# iot_macuman_board.net
KiCad netlist of a schematic drawn in Altium Designer
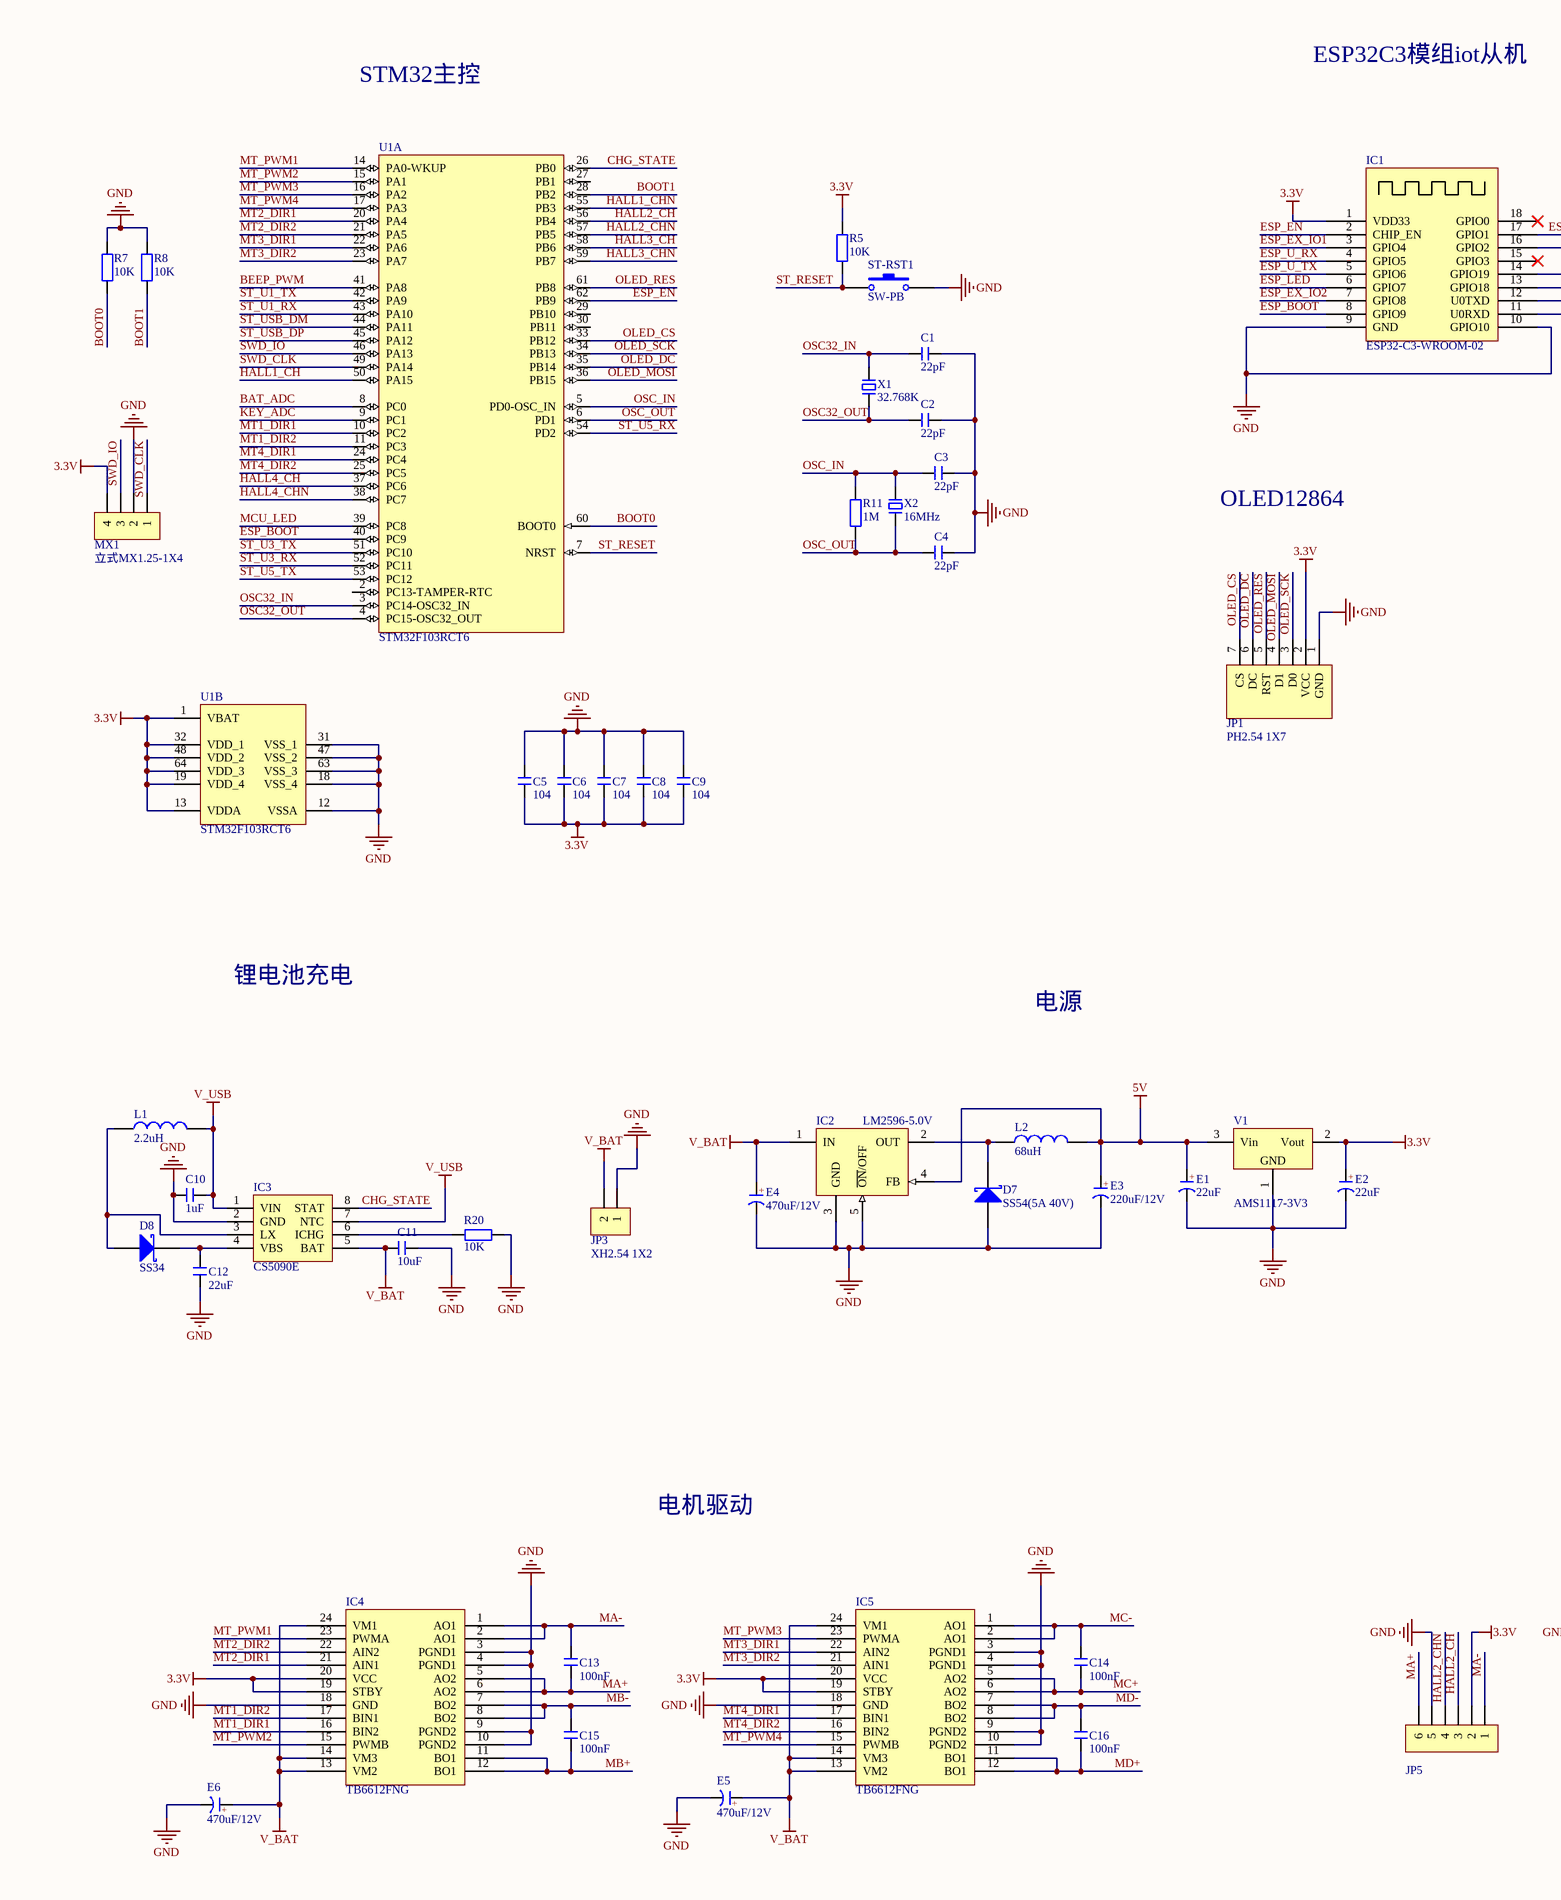
[diagram p0: iot_macuman_board.SchDoc, left]
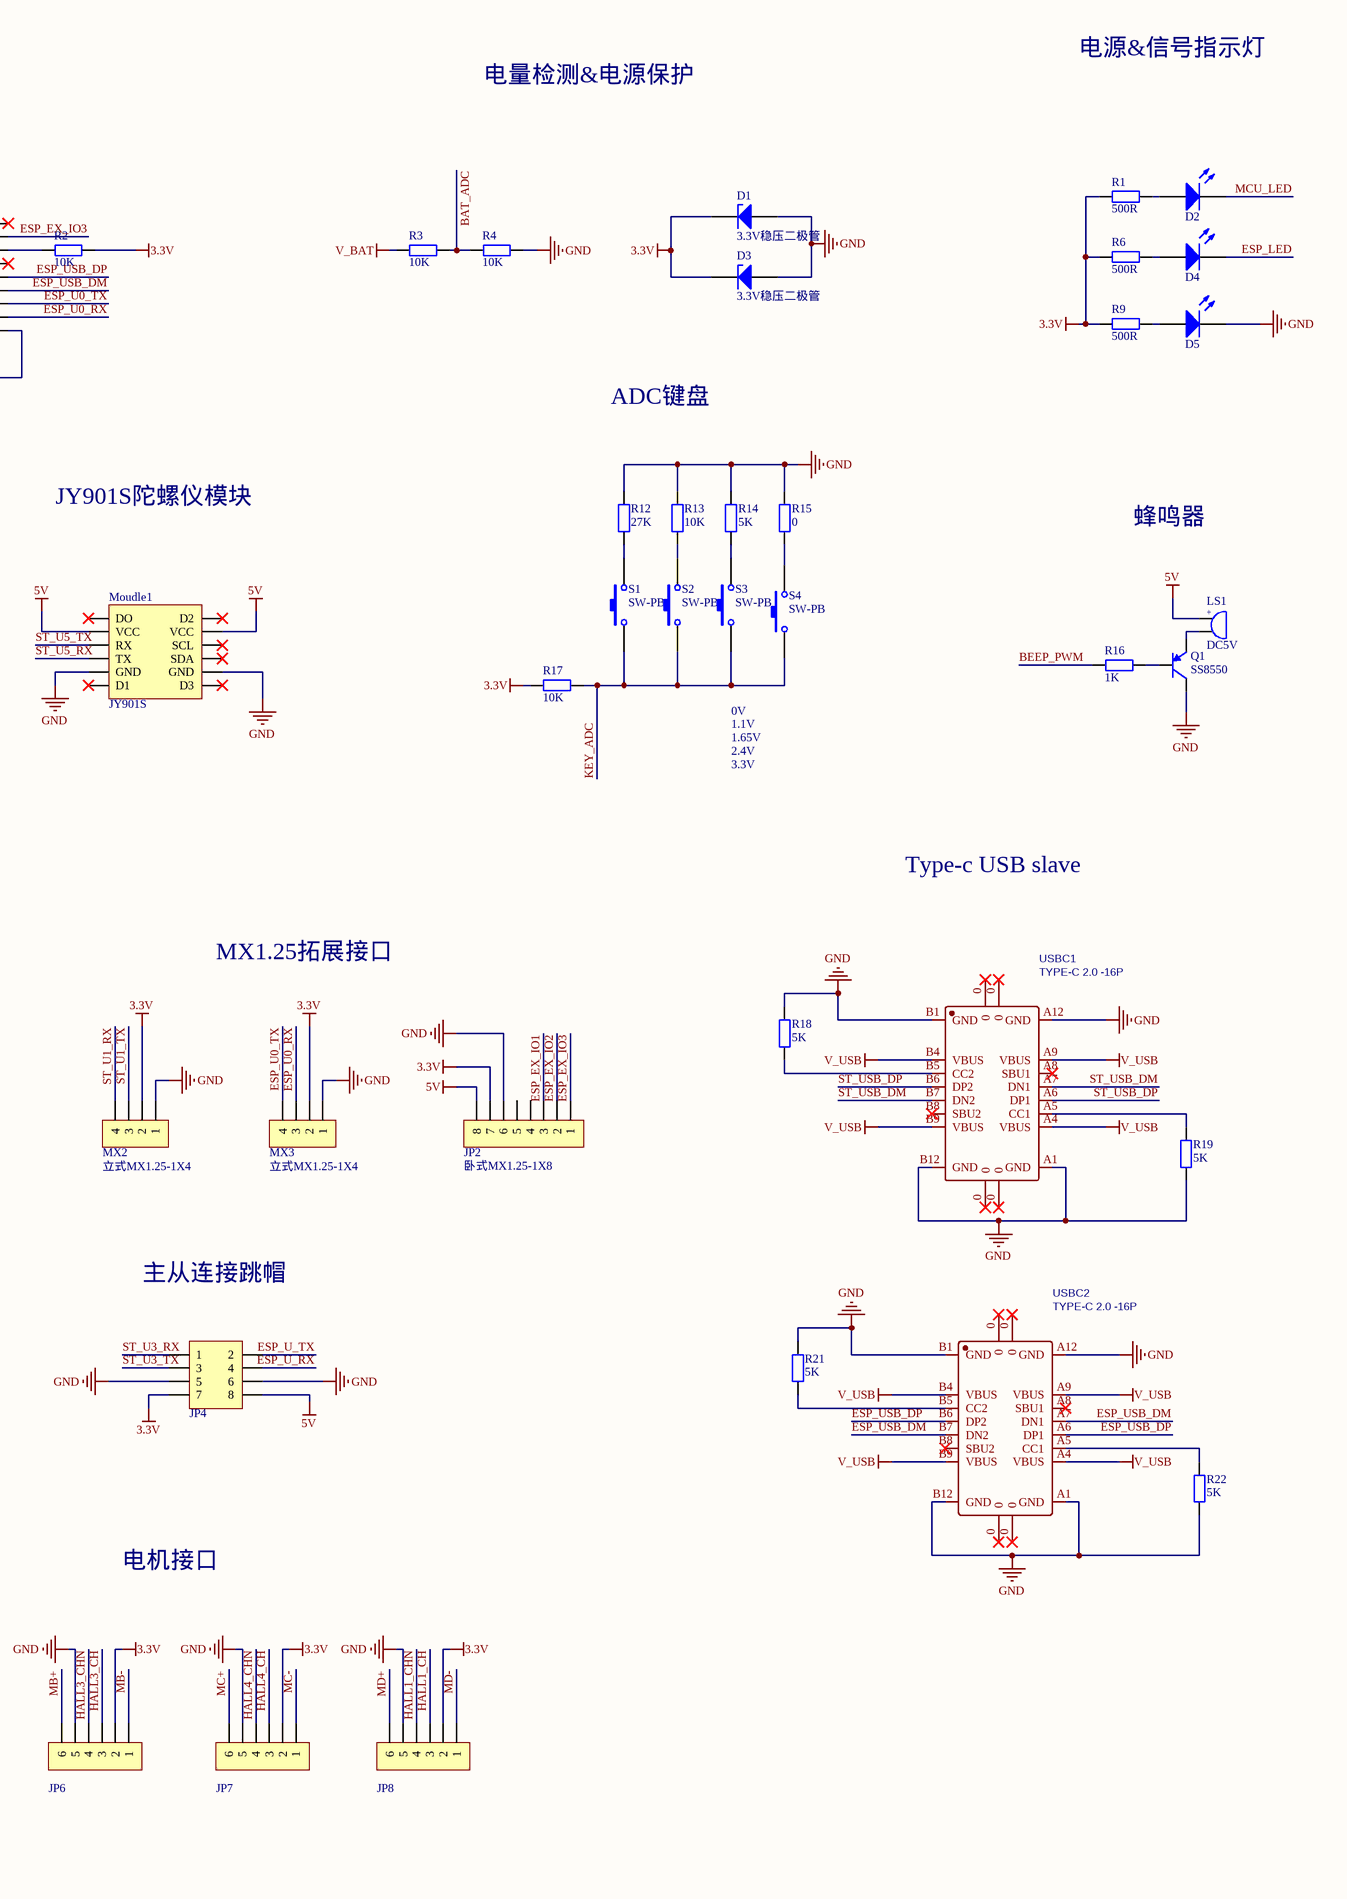
[diagram p1: iot_macuman_board.SchDoc, right]

(export (version "E")
  (design (tool "Eeschema 10.0.6"))
  (components
    (comp (ref "C1")
      (value "22pF")
      (footprint "C 0402")
      (description "贴片电容")
      (libsource (lib "核心板1") (part "C"))
    )
    (comp (ref "C2")
      (value "22pF")
      (footprint "C 0402")
      (description "贴片电容")
      (libsource (lib "核心板1") (part "C"))
    )
    (comp (ref "C3")
      (value "22pF")
      (footprint "C 0402")
      (description "贴片电容")
      (libsource (lib "核心板1") (part "C"))
    )
    (comp (ref "C4")
      (value "22pF")
      (footprint "C 0402")
      (description "贴片电容")
      (libsource (lib "核心板1") (part "C"))
    )
    (comp (ref "C5")
      (value "104")
      (footprint "C 0402")
      (description "贴片电容")
      (libsource (lib "核心板1") (part "C"))
    )
    (comp (ref "C6")
      (value "104")
      (footprint "C 0402")
      (description "贴片电容")
      (libsource (lib "核心板1") (part "C"))
    )
    (comp (ref "C7")
      (value "104")
      (footprint "C 0402")
      (description "贴片电容")
      (libsource (lib "核心板1") (part "C"))
    )
    (comp (ref "C8")
      (value "104")
      (footprint "C 0402")
      (description "贴片电容")
      (libsource (lib "核心板1") (part "C"))
    )
    (comp (ref "C9")
      (value "104")
      (footprint "C 0402")
      (description "贴片电容")
      (libsource (lib "核心板1") (part "C"))
    )
    (comp (ref "C10")
      (value "1uF")
      (footprint "C 0402")
      (description "贴片电容")
      (libsource (lib "核心板1") (part "C"))
    )
    (comp (ref "C11")
      (value "10uF")
      (footprint "C 0402")
      (description "贴片电容")
      (libsource (lib "核心板1") (part "C"))
    )
    (comp (ref "C12")
      (value "22uF")
      (footprint "C 0603_M")
      (description "贴片电容")
      (libsource (lib "核心板1") (part "C"))
    )
    (comp (ref "C13")
      (value "100nF")
      (footprint "C 0402")
      (description "贴片电容")
      (libsource (lib "核心板1") (part "C"))
    )
    (comp (ref "C14")
      (value "100nF")
      (footprint "C 0402")
      (description "贴片电容")
      (libsource (lib "核心板1") (part "C"))
    )
    (comp (ref "C15")
      (value "100nF")
      (footprint "C 0402")
      (description "贴片电容")
      (libsource (lib "核心板1") (part "C"))
    )
    (comp (ref "C16")
      (value "100nF")
      (footprint "C 0402")
      (description "贴片电容")
      (libsource (lib "核心板1") (part "C"))
    )
    (comp (ref "D1")
      (value "3.3V稳压二极管")
      (footprint "LL34")
      (description "Zener Diode")
      (libsource (lib "核心板1") (part "稳压二极管"))
    )
    (comp (ref "D2")
      (value "LED")
      (footprint "LED 0805G")
      (description "发光二极管")
      (libsource (lib "核心板1") (part "LED"))
    )
    (comp (ref "D3")
      (value "3.3V稳压二极管")
      (footprint "LL34")
      (description "Zener Diode")
      (libsource (lib "核心板1") (part "稳压二极管"))
    )
    (comp (ref "D4")
      (value "LED")
      (footprint "LED 0805G")
      (description "发光二极管")
      (libsource (lib "核心板1") (part "LED"))
    )
    (comp (ref "D5")
      (value "LED")
      (footprint "LED 0805G")
      (description "发光二极管")
      (libsource (lib "核心板1") (part "LED"))
    )
    (comp (ref "D7")
      (value "SS54(5A 40V)")
      (footprint "SMB")
      (description "肖特基二极管")
      (libsource (lib "核心板1") (part "1N5819"))
    )
    (comp (ref "D8")
      (value "SS34")
      (footprint "SMA")
      (description "肖特基二极管")
      (libsource (lib "核心板1") (part "SS34"))
    )
    (comp (ref "E1")
      (value "22uF")
      (footprint "CM C(5*5.4)")
      (description "贴片固态电容")
      (libsource (lib "0.1 - 电阻-电容-电感") (part "CS_SMD"))
    )
    (comp (ref "E2")
      (value "22uF")
      (footprint "CM C(5*5.4)")
      (description "贴片固态电容")
      (libsource (lib "0.1 - 电阻-电容-电感") (part "CS_SMD"))
    )
    (comp (ref "E3")
      (value "220uF/12V")
      (footprint "CM C(5*5.4)")
      (description "贴片固态电容")
      (libsource (lib "0.1 - 电阻-电容-电感") (part "CS_SMD"))
    )
    (comp (ref "E4")
      (value "470uF/12V")
      (footprint "CM E(8*10.2)")
      (description "贴片电解电容")
      (libsource (lib "*") (part "CE_SMD"))
    )
    (comp (ref "E5")
      (value "470uF/12V")
      (footprint "CM E(8*10.2)")
      (description "贴片电解电容")
      (libsource (lib "") (part "CE_SMD_1"))
    )
    (comp (ref "E6")
      (value "470uF/12V")
      (footprint "CM E(8*10.2)")
      (description "贴片电解电容")
      (libsource (lib "") (part "CE_SMD_1"))
    )
    (comp (ref "IC1")
      (value "ESP32-C3-WROOM-02")
      (footprint "ESP32-C3-WROOM-02")
      (description "ESP32C3模组")
      (libsource (lib "核心板1") (part "ESP32-C3-WROOM-02"))
    )
    (comp (ref "IC2")
      (value "LM2596-5.0V")
      (footprint "TO263-5A")
      (description "DC降压芯片")
      (libsource (lib "核心板1") (part "LM2596-5.0"))
    )
    (comp (ref "IC3")
      (value "CS5090E")
      (footprint "SOP8_M")
      (description "8.4V锂电池充电芯片")
      (libsource (lib "核心板1") (part "CS5090E"))
    )
    (comp (ref "IC4")
      (value "TB6612FNG")
      (footprint "SSOP24")
      (description "电机驱动IC")
      (libsource (lib "核心板1") (part "TB6612FNG"))
    )
    (comp (ref "IC5")
      (value "TB6612FNG")
      (footprint "SSOP24")
      (description "电机驱动IC")
      (libsource (lib "核心板1") (part "TB6612FNG"))
    )
    (comp (ref "JP1")
      (value "PH2.54 1X7")
      (footprint "HDR2.54-LI-7P")
      (description "12864 点阵屏")
      (libsource (lib "核心板1") (part "OLED 1.3-12864_7pin"))
    )
    (comp (ref "JP2")
      (value "卧式MX1.25-1X8")
      (footprint "MX 1.25-WS-8P")
      (description "8P接插件")
      (libsource (lib "iot_macuman_board") (part "Header 8"))
    )
    (comp (ref "JP3")
      (value "XH2.54 1X2")
      (footprint "XH2.54-LI-2P")
      (libsource (lib "核心板1") (part "Header 2"))
    )
    (comp (ref "JP4")
      (value "PH2.54 4X2")
      (footprint "HDR2.54-LI-2X4P")
      (description "4*2P接插件")
      (libsource (lib "核心板1") (part "Header 4X2"))
    )
    (comp (ref "JP5")
      (value "电机接口")
      (footprint "XH2.54-WI-6P")
      (description "6P接插件")
      (libsource (lib "核心板1") (part "Header 6"))
    )
    (comp (ref "JP6")
      (value "电机接口")
      (footprint "XH2.54-WI-6P")
      (description "6P接插件")
      (libsource (lib "核心板1") (part "Header 6"))
    )
    (comp (ref "JP7")
      (value "电机接口")
      (footprint "XH2.54-WI-6P")
      (description "6P接插件")
      (libsource (lib "核心板1") (part "Header 6"))
    )
    (comp (ref "JP8")
      (value "电机接口")
      (footprint "XH2.54-WI-6P")
      (description "6P接插件")
      (libsource (lib "核心板1") (part "Header 6"))
    )
    (comp (ref "L1")
      (value "2.2uH")
      (footprint "CD32")
      (description "小功率贴片电感")
      (libsource (lib "核心板1") (part "L"))
    )
    (comp (ref "L2")
      (value "68uH")
      (footprint "CD32")
      (description "小功率贴片电感")
      (libsource (lib "核心板1") (part "L"))
    )
    (comp (ref "LS1")
      (value "DC5V")
      (footprint "蜂鸣器(脚距6.5)")
      (description "蜂鸣器")
      (libsource (lib "核心板1") (part "BEEP"))
    )
    (comp (ref "Moudle1")
      (value "JY901S")
      (footprint "JY901S")
      (libsource (lib "iot_macuman_board") (part "JY901S"))
    )
    (comp (ref "MX1")
      (value "立式MX1.25-1X4")
      (footprint "MX 1.25-LS-4P")
      (description "4P接插件")
      (libsource (lib "核心板1") (part "Header 4"))
    )
    (comp (ref "MX2")
      (value "立式MX1.25-1X4")
      (footprint "MX 1.25-LS-4P")
      (description "4P接插件")
      (libsource (lib "核心板1") (part "Header 4"))
    )
    (comp (ref "MX3")
      (value "立式MX1.25-1X4")
      (footprint "MX 1.25-LS-4P")
      (description "4P接插件")
      (libsource (lib "核心板1") (part "Header 4"))
    )
    (comp (ref "Q1")
      (value "SS8550")
      (footprint "sot-23")
      (description "高频放大-PNP型")
      (libsource (lib "*") (part "8550-SMD"))
    )
    (comp (ref "R1")
      (value "500R")
      (footprint "R 0402")
      (description "贴片电阻")
      (libsource (lib "核心板1") (part "R"))
    )
    (comp (ref "R2")
      (value "10K")
      (footprint "R 0402")
      (description "贴片电阻")
      (libsource (lib "核心板1") (part "R"))
    )
    (comp (ref "R3")
      (value "10K")
      (footprint "R 0402")
      (description "贴片电阻")
      (libsource (lib "核心板1") (part "R"))
    )
    (comp (ref "R4")
      (value "10K")
      (footprint "R 0402")
      (description "贴片电阻")
      (libsource (lib "核心板1") (part "R"))
    )
    (comp (ref "R5")
      (value "10K")
      (footprint "R 0402")
      (description "贴片电阻")
      (libsource (lib "核心板1") (part "R"))
    )
    (comp (ref "R6")
      (value "500R")
      (footprint "R 0402")
      (description "贴片电阻")
      (libsource (lib "核心板1") (part "R"))
    )
    (comp (ref "R7")
      (value "10K")
      (footprint "R 0402")
      (description "贴片电阻")
      (libsource (lib "核心板1") (part "R"))
    )
    (comp (ref "R8")
      (value "10K")
      (footprint "R 0402")
      (description "贴片电阻")
      (libsource (lib "核心板1") (part "R"))
    )
    (comp (ref "R9")
      (value "500R")
      (footprint "R 0402")
      (description "贴片电阻")
      (libsource (lib "核心板1") (part "R"))
    )
    (comp (ref "R11")
      (value "1M")
      (footprint "R 0402")
      (description "贴片电阻")
      (libsource (lib "核心板1") (part "R"))
    )
    (comp (ref "R12")
      (value "27K")
      (footprint "R 0402")
      (description "贴片电阻")
      (libsource (lib "核心板1") (part "R"))
    )
    (comp (ref "R13")
      (value "10K")
      (footprint "R 0402")
      (description "贴片电阻")
      (libsource (lib "核心板1") (part "R"))
    )
    (comp (ref "R14")
      (value "5K")
      (footprint "R 0402")
      (description "贴片电阻")
      (libsource (lib "核心板1") (part "R"))
    )
    (comp (ref "R15")
      (value "0")
      (footprint "R 0402")
      (description "贴片电阻")
      (libsource (lib "核心板1") (part "R"))
    )
    (comp (ref "R16")
      (value "1K")
      (footprint "R 0402")
      (description "贴片电阻")
      (libsource (lib "核心板1") (part "R"))
    )
    (comp (ref "R17")
      (value "10K")
      (footprint "R 0402")
      (description "贴片电阻")
      (libsource (lib "核心板1") (part "R"))
    )
    (comp (ref "R18")
      (value "5K")
      (footprint "R 0402")
      (description "贴片电阻")
      (libsource (lib "核心板1") (part "R"))
    )
    (comp (ref "R19")
      (value "5K")
      (footprint "R 0402")
      (description "贴片电阻")
      (libsource (lib "核心板1") (part "R"))
    )
    (comp (ref "R20")
      (value "10K")
      (footprint "R 0402")
      (description "贴片电阻")
      (libsource (lib "核心板1") (part "R"))
    )
    (comp (ref "R21")
      (value "5K")
      (footprint "R 0402")
      (description "贴片电阻")
      (libsource (lib "核心板1") (part "R"))
    )
    (comp (ref "R22")
      (value "5K")
      (footprint "R 0402")
      (description "贴片电阻")
      (libsource (lib "核心板1") (part "R"))
    )
    (comp (ref "S1")
      (value "SW-PB")
      (footprint "TSW SMD-3*6*2.5")
      (description "微动开关")
      (libsource (lib "核心板1") (part "SW-PB"))
    )
    (comp (ref "S2")
      (value "SW-PB")
      (footprint "TSW SMD-3*6*2.5")
      (description "微动开关")
      (libsource (lib "核心板1") (part "SW-PB"))
    )
    (comp (ref "S3")
      (value "SW-PB")
      (footprint "TSW SMD-3*6*2.5")
      (description "微动开关")
      (libsource (lib "核心板1") (part "SW-PB"))
    )
    (comp (ref "S4")
      (value "SW-PB")
      (footprint "TSW SMD-3*6*2.5")
      (description "微动开关")
      (libsource (lib "核心板1") (part "SW-PB"))
    )
    (comp (ref "ST-RST1")
      (value "SW-PB")
      (footprint "TSW SMD-3*6*2.5")
      (description "微动开关")
      (libsource (lib "核心板1") (part "SW-PB"))
    )
    (comp (ref "U1")
      (value "STM32F103RCT6")
      (footprint "LQFP64-10*10")
      (libsource (lib "核心板1") (part "STM32F103RCT6"))
    )
    (comp (ref "USBC1")
      (value "TYPE-C 2.0 -16P")
      (footprint "USB-C-SMD_TYPE-C-USB-5")
      (description "USB2.0 Type-C 母座 16Pin")
      (libsource (lib "核心板1") (part "USB2.0 Type-C 16Pin母座"))
    )
    (comp (ref "USBC2")
      (value "TYPE-C 2.0 -16P")
      (footprint "USB-C-SMD_TYPE-C-USB-5")
      (description "USB2.0 Type-C 母座 16Pin")
      (libsource (lib "核心板1") (part "USB2.0 Type-C 16Pin母座"))
    )
    (comp (ref "V1")
      (value "AMS1117-3V3")
      (footprint "SOT223_L")
      (description "三端稳压芯片")
      (libsource (lib "核心板1") (part "AMS1117"))
    )
    (comp (ref "X1")
      (value "32.768K")
      (footprint "OSC 3215-2P")
      (description "2脚无源脚晶振")
      (libsource (lib "Schlib1") (part "XTAL-2P"))
    )
    (comp (ref "X2")
      (value "16MHz")
      (footprint "OSC 5032-2P")
      (description "2脚无源脚晶振")
      (libsource (lib "Schlib1") (part "XTAL-2P"))
    )
  )
  (nets
    (net (code "1") (name "/BAT_ADC") (class "Default")
      (node (ref "R3") (pin "1") (pinfunction "1_1") (pintype "passive"))
      (node (ref "R4") (pin "2") (pinfunction "2_2") (pintype "passive"))
      (node (ref "U1") (pin "8") (pinfunction "PC0_8") (pintype "bidirectional"))
    )
    (net (code "2") (name "/BEEP_PWM") (class "Default")
      (node (ref "R16") (pin "2") (pinfunction "2_2") (pintype "passive"))
      (node (ref "U1") (pin "41") (pinfunction "PA8_41") (pintype "bidirectional"))
    )
    (net (code "3") (name "/BOOT0") (class "Default")
      (node (ref "R7") (pin "2") (pinfunction "2_2") (pintype "passive"))
      (node (ref "U1") (pin "60") (pinfunction "BOOT0_60") (pintype "input"))
    )
    (net (code "4") (name "/BOOT1") (class "Default")
      (node (ref "R8") (pin "2") (pinfunction "2_2") (pintype "passive"))
      (node (ref "U1") (pin "28") (pinfunction "PB2_28") (pintype "bidirectional"))
    )
    (net (code "5") (name "/CHG_STATE") (class "Default")
      (node (ref "IC3") (pin "8") (pinfunction "STAT_8") (pintype "passive"))
      (node (ref "U1") (pin "26") (pinfunction "PB0_26") (pintype "bidirectional"))
    )
    (net (code "6") (name "/ESP_BOOT") (class "Default")
      (node (ref "IC1") (pin "8") (pinfunction "GPIO9_8") (pintype "passive"))
      (node (ref "U1") (pin "40") (pinfunction "PC9_40") (pintype "bidirectional"))
    )
    (net (code "7") (name "/ESP_EN") (class "Default")
      (node (ref "IC1") (pin "2") (pinfunction "CHIP_EN_2") (pintype "passive"))
      (node (ref "U1") (pin "62") (pinfunction "PB9_62") (pintype "bidirectional"))
    )
    (net (code "8") (name "/ESP_EX_IO1") (class "Default")
      (node (ref "IC1") (pin "3") (pinfunction "GPIO4_3") (pintype "passive"))
      (node (ref "JP2") (pin "3") (pinfunction "3_3") (pintype "passive"))
    )
    (net (code "9") (name "/ESP_EX_IO2") (class "Default")
      (node (ref "IC1") (pin "7") (pinfunction "GPIO8_7") (pintype "passive"))
      (node (ref "JP2") (pin "2") (pinfunction "2_2") (pintype "passive"))
    )
    (net (code "10") (name "/ESP_EX_IO3") (class "Default")
      (node (ref "IC1") (pin "17") (pinfunction "GPIO1_17") (pintype "passive"))
      (node (ref "JP2") (pin "1") (pinfunction "1_1") (pintype "passive"))
    )
    (net (code "11") (name "/ESP_LED") (class "Default")
      (node (ref "D4") (pin "2") (pinfunction "K_2") (pintype "passive"))
      (node (ref "IC1") (pin "6") (pinfunction "GPIO7_6") (pintype "passive"))
    )
    (net (code "12") (name "/ESP_U0_RX") (class "Default")
      (node (ref "IC1") (pin "11") (pinfunction "U0RXD_11") (pintype "passive"))
      (node (ref "MX3") (pin "3") (pinfunction "3_3") (pintype "passive"))
    )
    (net (code "13") (name "/ESP_U0_TX") (class "Default")
      (node (ref "IC1") (pin "12") (pinfunction "U0TXD_12") (pintype "passive"))
      (node (ref "MX3") (pin "4") (pinfunction "4_4") (pintype "passive"))
    )
    (net (code "14") (name "/ESP_USB_DM") (class "Default")
      (node (ref "IC1") (pin "13") (pinfunction "GPIO18_13") (pintype "passive"))
      (node (ref "USBC2") (pin "A7") (pinfunction "DN1_A7") (pintype "passive"))
      (node (ref "USBC2") (pin "B7") (pinfunction "DN2_B7") (pintype "passive"))
    )
    (net (code "15") (name "/ESP_USB_DP") (class "Default")
      (node (ref "IC1") (pin "14") (pinfunction "GPIO19_14") (pintype "passive"))
      (node (ref "USBC2") (pin "A6") (pinfunction "DP1_A6") (pintype "passive"))
      (node (ref "USBC2") (pin "B6") (pinfunction "DP2_B6") (pintype "passive"))
    )
    (net (code "16") (name "/ESP_U_RX") (class "Default")
      (node (ref "IC1") (pin "4") (pinfunction "GPIO5_4") (pintype "passive"))
      (node (ref "JP4") (pin "4") (pinfunction "4_4") (pintype "passive"))
    )
    (net (code "17") (name "/ESP_U_TX") (class "Default")
      (node (ref "IC1") (pin "5") (pinfunction "GPIO6_5") (pintype "passive"))
      (node (ref "JP4") (pin "2") (pinfunction "2_2") (pintype "passive"))
    )
    (net (code "18") (name "/HALL1_CH") (class "Default")
      (node (ref "JP8") (pin "3") (pinfunction "3_3") (pintype "passive"))
      (node (ref "U1") (pin "50") (pinfunction "PA15_50") (pintype "bidirectional"))
    )
    (net (code "19") (name "/HALL1_CHN") (class "Default")
      (node (ref "JP8") (pin "4") (pinfunction "4_4") (pintype "passive"))
      (node (ref "U1") (pin "55") (pinfunction "PB3_55") (pintype "bidirectional"))
    )
    (net (code "20") (name "/HALL2_CH") (class "Default")
      (node (ref "JP5") (pin "3") (pinfunction "3_3") (pintype "passive"))
      (node (ref "U1") (pin "56") (pinfunction "PB4_56") (pintype "bidirectional"))
    )
    (net (code "21") (name "/HALL2_CHN") (class "Default")
      (node (ref "JP5") (pin "4") (pinfunction "4_4") (pintype "passive"))
      (node (ref "U1") (pin "57") (pinfunction "PB5_57") (pintype "bidirectional"))
    )
    (net (code "22") (name "/HALL3_CH") (class "Default")
      (node (ref "JP6") (pin "3") (pinfunction "3_3") (pintype "passive"))
      (node (ref "U1") (pin "58") (pinfunction "PB6_58") (pintype "bidirectional"))
    )
    (net (code "23") (name "/HALL3_CHN") (class "Default")
      (node (ref "JP6") (pin "4") (pinfunction "4_4") (pintype "passive"))
      (node (ref "U1") (pin "59") (pinfunction "PB7_59") (pintype "bidirectional"))
    )
    (net (code "24") (name "/HALL4_CH") (class "Default")
      (node (ref "JP7") (pin "3") (pinfunction "3_3") (pintype "passive"))
      (node (ref "U1") (pin "37") (pinfunction "PC6_37") (pintype "bidirectional"))
    )
    (net (code "25") (name "/HALL4_CHN") (class "Default")
      (node (ref "JP7") (pin "4") (pinfunction "4_4") (pintype "passive"))
      (node (ref "U1") (pin "38") (pinfunction "PC7_38") (pintype "bidirectional"))
    )
    (net (code "26") (name "/KEY_ADC") (class "Default")
      (node (ref "R17") (pin "2") (pinfunction "2_2") (pintype "passive"))
      (node (ref "S1") (pin "1") (pinfunction "1_1") (pintype "passive"))
      (node (ref "S2") (pin "1") (pinfunction "1_1") (pintype "passive"))
      (node (ref "S3") (pin "1") (pinfunction "1_1") (pintype "passive"))
      (node (ref "S4") (pin "1") (pinfunction "1_1") (pintype "passive"))
      (node (ref "U1") (pin "9") (pinfunction "PC1_9") (pintype "bidirectional"))
    )
    (net (code "27") (name "/MA+") (class "Default")
      (node (ref "C13") (pin "2") (pinfunction "2_2") (pintype "passive"))
      (node (ref "IC4") (pin "5") (pinfunction "AO2_5") (pintype "passive"))
      (node (ref "IC4") (pin "6") (pinfunction "AO2_6") (pintype "passive"))
      (node (ref "JP5") (pin "6") (pinfunction "6_6") (pintype "passive"))
    )
    (net (code "28") (name "/MA-") (class "Default")
      (node (ref "C13") (pin "1") (pinfunction "1_1") (pintype "passive"))
      (node (ref "IC4") (pin "1") (pinfunction "AO1_1") (pintype "passive"))
      (node (ref "IC4") (pin "2") (pinfunction "AO1_2") (pintype "passive"))
      (node (ref "JP5") (pin "1") (pinfunction "1_1") (pintype "passive"))
    )
    (net (code "29") (name "/MB+") (class "Default")
      (node (ref "C15") (pin "2") (pinfunction "2_2") (pintype "passive"))
      (node (ref "IC4") (pin "11") (pinfunction "BO1_11") (pintype "passive"))
      (node (ref "IC4") (pin "12") (pinfunction "BO1_12") (pintype "passive"))
      (node (ref "JP6") (pin "6") (pinfunction "6_6") (pintype "passive"))
    )
    (net (code "30") (name "/MB-") (class "Default")
      (node (ref "C15") (pin "1") (pinfunction "1_1") (pintype "passive"))
      (node (ref "IC4") (pin "7") (pinfunction "BO2_7") (pintype "passive"))
      (node (ref "IC4") (pin "8") (pinfunction "BO2_8") (pintype "passive"))
      (node (ref "JP6") (pin "1") (pinfunction "1_1") (pintype "passive"))
    )
    (net (code "31") (name "/MC+") (class "Default")
      (node (ref "C14") (pin "2") (pinfunction "2_2") (pintype "passive"))
      (node (ref "IC5") (pin "5") (pinfunction "AO2_5") (pintype "passive"))
      (node (ref "IC5") (pin "6") (pinfunction "AO2_6") (pintype "passive"))
      (node (ref "JP7") (pin "6") (pinfunction "6_6") (pintype "passive"))
    )
    (net (code "32") (name "/MC-") (class "Default")
      (node (ref "C14") (pin "1") (pinfunction "1_1") (pintype "passive"))
      (node (ref "IC5") (pin "1") (pinfunction "AO1_1") (pintype "passive"))
      (node (ref "IC5") (pin "2") (pinfunction "AO1_2") (pintype "passive"))
      (node (ref "JP7") (pin "1") (pinfunction "1_1") (pintype "passive"))
    )
    (net (code "33") (name "/MCU_LED") (class "Default")
      (node (ref "D2") (pin "2") (pinfunction "K_2") (pintype "passive"))
      (node (ref "U1") (pin "39") (pinfunction "PC8_39") (pintype "bidirectional"))
    )
    (net (code "34") (name "/MD+") (class "Default")
      (node (ref "C16") (pin "2") (pinfunction "2_2") (pintype "passive"))
      (node (ref "IC5") (pin "11") (pinfunction "BO1_11") (pintype "passive"))
      (node (ref "IC5") (pin "12") (pinfunction "BO1_12") (pintype "passive"))
      (node (ref "JP8") (pin "6") (pinfunction "6_6") (pintype "passive"))
    )
    (net (code "35") (name "/MD-") (class "Default")
      (node (ref "C16") (pin "1") (pinfunction "1_1") (pintype "passive"))
      (node (ref "IC5") (pin "7") (pinfunction "BO2_7") (pintype "passive"))
      (node (ref "IC5") (pin "8") (pinfunction "BO2_8") (pintype "passive"))
      (node (ref "JP8") (pin "1") (pinfunction "1_1") (pintype "passive"))
    )
    (net (code "36") (name "/MT1_DIR1") (class "Default")
      (node (ref "IC4") (pin "16") (pinfunction "BIN2_16") (pintype "passive"))
      (node (ref "U1") (pin "10") (pinfunction "PC2_10") (pintype "bidirectional"))
    )
    (net (code "37") (name "/MT1_DIR2") (class "Default")
      (node (ref "IC4") (pin "17") (pinfunction "BIN1_17") (pintype "passive"))
      (node (ref "U1") (pin "11") (pinfunction "PC3_11") (pintype "bidirectional"))
    )
    (net (code "38") (name "/MT2_DIR1") (class "Default")
      (node (ref "IC4") (pin "21") (pinfunction "AIN1_21") (pintype "passive"))
      (node (ref "U1") (pin "20") (pinfunction "PA4_20") (pintype "bidirectional"))
    )
    (net (code "39") (name "/MT2_DIR2") (class "Default")
      (node (ref "IC4") (pin "22") (pinfunction "AIN2_22") (pintype "passive"))
      (node (ref "U1") (pin "21") (pinfunction "PA5_21") (pintype "bidirectional"))
    )
    (net (code "40") (name "/MT3_DIR1") (class "Default")
      (node (ref "IC5") (pin "22") (pinfunction "AIN2_22") (pintype "passive"))
      (node (ref "U1") (pin "22") (pinfunction "PA6_22") (pintype "bidirectional"))
    )
    (net (code "41") (name "/MT3_DIR2") (class "Default")
      (node (ref "IC5") (pin "21") (pinfunction "AIN1_21") (pintype "passive"))
      (node (ref "U1") (pin "23") (pinfunction "PA7_23") (pintype "bidirectional"))
    )
    (net (code "42") (name "/MT4_DIR1") (class "Default")
      (node (ref "IC5") (pin "17") (pinfunction "BIN1_17") (pintype "passive"))
      (node (ref "U1") (pin "24") (pinfunction "PC4_24") (pintype "bidirectional"))
    )
    (net (code "43") (name "/MT4_DIR2") (class "Default")
      (node (ref "IC5") (pin "16") (pinfunction "BIN2_16") (pintype "passive"))
      (node (ref "U1") (pin "25") (pinfunction "PC5_25") (pintype "bidirectional"))
    )
    (net (code "44") (name "/MT_PWM1") (class "Default")
      (node (ref "IC4") (pin "23") (pinfunction "PWMA_23") (pintype "passive"))
      (node (ref "U1") (pin "14") (pinfunction "PA0-WKUP_14") (pintype "bidirectional"))
    )
    (net (code "45") (name "/MT_PWM2") (class "Default")
      (node (ref "IC4") (pin "15") (pinfunction "PWMB_15") (pintype "passive"))
      (node (ref "U1") (pin "15") (pinfunction "PA1_15") (pintype "bidirectional"))
    )
    (net (code "46") (name "/MT_PWM3") (class "Default")
      (node (ref "IC5") (pin "23") (pinfunction "PWMA_23") (pintype "passive"))
      (node (ref "U1") (pin "16") (pinfunction "PA2_16") (pintype "bidirectional"))
    )
    (net (code "47") (name "/MT_PWM4") (class "Default")
      (node (ref "IC5") (pin "15") (pinfunction "PWMB_15") (pintype "passive"))
      (node (ref "U1") (pin "17") (pinfunction "PA3_17") (pintype "bidirectional"))
    )
    (net (code "48") (name "/OLED_CS") (class "Default")
      (node (ref "JP1") (pin "7") (pinfunction "CS_7") (pintype "passive"))
      (node (ref "U1") (pin "33") (pinfunction "PB12_33") (pintype "bidirectional"))
    )
    (net (code "49") (name "/OLED_DC") (class "Default")
      (node (ref "JP1") (pin "6") (pinfunction "DC_6") (pintype "passive"))
      (node (ref "U1") (pin "35") (pinfunction "PB14_35") (pintype "bidirectional"))
    )
    (net (code "50") (name "/OLED_MOSI") (class "Default")
      (node (ref "JP1") (pin "4") (pinfunction "D1_4") (pintype "passive"))
      (node (ref "U1") (pin "36") (pinfunction "PB15_36") (pintype "bidirectional"))
    )
    (net (code "51") (name "/OLED_RES") (class "Default")
      (node (ref "JP1") (pin "5") (pinfunction "RST_5") (pintype "passive"))
      (node (ref "U1") (pin "61") (pinfunction "PB8_61") (pintype "bidirectional"))
    )
    (net (code "52") (name "/OLED_SCK") (class "Default")
      (node (ref "JP1") (pin "3") (pinfunction "D0_3") (pintype "passive"))
      (node (ref "U1") (pin "34") (pinfunction "PB13_34") (pintype "bidirectional"))
    )
    (net (code "53") (name "/OSC32_IN") (class "Default")
      (node (ref "C1") (pin "2") (pinfunction "2_2") (pintype "passive"))
      (node (ref "U1") (pin "3") (pinfunction "PC14-OSC32_IN_3") (pintype "bidirectional"))
      (node (ref "X1") (pin "1") (pinfunction "1_1") (pintype "passive"))
    )
    (net (code "54") (name "/OSC32_OUT") (class "Default")
      (node (ref "C2") (pin "2") (pinfunction "2_2") (pintype "passive"))
      (node (ref "U1") (pin "4") (pinfunction "PC15-OSC32_OUT_4") (pintype "bidirectional"))
      (node (ref "X1") (pin "2") (pinfunction "2_2") (pintype "passive"))
    )
    (net (code "55") (name "/OSC_IN") (class "Default")
      (node (ref "C3") (pin "2") (pinfunction "2_2") (pintype "passive"))
      (node (ref "R11") (pin "2") (pinfunction "2_2") (pintype "passive"))
      (node (ref "U1") (pin "5") (pinfunction "PD0-OSC_IN_5") (pintype "bidirectional"))
      (node (ref "X2") (pin "1") (pinfunction "1_1") (pintype "passive"))
    )
    (net (code "56") (name "/OSC_OUT") (class "Default")
      (node (ref "C4") (pin "2") (pinfunction "2_2") (pintype "passive"))
      (node (ref "R11") (pin "1") (pinfunction "1_1") (pintype "passive"))
      (node (ref "U1") (pin "6") (pinfunction "PD1_6") (pintype "bidirectional"))
      (node (ref "X2") (pin "2") (pinfunction "2_2") (pintype "passive"))
    )
    (net (code "57") (name "/ST_RESET") (class "Default")
      (node (ref "R5") (pin "2") (pinfunction "2_2") (pintype "passive"))
      (node (ref "ST-RST1") (pin "1") (pinfunction "1_1") (pintype "passive"))
      (node (ref "U1") (pin "7") (pinfunction "NRST_7") (pintype "bidirectional"))
    )
    (net (code "58") (name "/ST_U1_RX") (class "Default")
      (node (ref "MX2") (pin "4") (pinfunction "4_4") (pintype "passive"))
      (node (ref "U1") (pin "43") (pinfunction "PA10_43") (pintype "bidirectional"))
    )
    (net (code "59") (name "/ST_U1_TX") (class "Default")
      (node (ref "MX2") (pin "3") (pinfunction "3_3") (pintype "passive"))
      (node (ref "U1") (pin "42") (pinfunction "PA9_42") (pintype "bidirectional"))
    )
    (net (code "60") (name "/ST_U3_RX") (class "Default")
      (node (ref "JP4") (pin "1") (pinfunction "1_1") (pintype "passive"))
      (node (ref "U1") (pin "52") (pinfunction "PC11_52") (pintype "bidirectional"))
    )
    (net (code "61") (name "/ST_U3_TX") (class "Default")
      (node (ref "JP4") (pin "3") (pinfunction "3_3") (pintype "passive"))
      (node (ref "U1") (pin "51") (pinfunction "PC10_51") (pintype "bidirectional"))
    )
    (net (code "62") (name "/ST_U5_RX") (class "Default")
      (node (ref "Moudle1") (pin "4") (pinfunction "TX_4") (pintype "passive"))
      (node (ref "U1") (pin "54") (pinfunction "PD2_54") (pintype "bidirectional"))
    )
    (net (code "63") (name "/ST_U5_TX") (class "Default")
      (node (ref "Moudle1") (pin "3") (pinfunction "RX_3") (pintype "passive"))
      (node (ref "U1") (pin "53") (pinfunction "PC12_53") (pintype "bidirectional"))
    )
    (net (code "64") (name "/ST_USB_DM") (class "Default")
      (node (ref "U1") (pin "44") (pinfunction "PA11_44") (pintype "bidirectional"))
      (node (ref "USBC1") (pin "A7") (pinfunction "DN1_A7") (pintype "passive"))
      (node (ref "USBC1") (pin "B7") (pinfunction "DN2_B7") (pintype "passive"))
    )
    (net (code "65") (name "/ST_USB_DP") (class "Default")
      (node (ref "U1") (pin "45") (pinfunction "PA12_45") (pintype "bidirectional"))
      (node (ref "USBC1") (pin "A6") (pinfunction "DP1_A6") (pintype "passive"))
      (node (ref "USBC1") (pin "B6") (pinfunction "DP2_B6") (pintype "passive"))
    )
    (net (code "66") (name "/SWD_CLK") (class "Default")
      (node (ref "MX1") (pin "1") (pinfunction "1_1") (pintype "passive"))
      (node (ref "U1") (pin "49") (pinfunction "PA14_49") (pintype "bidirectional"))
    )
    (net (code "67") (name "/SWD_IO") (class "Default")
      (node (ref "MX1") (pin "3") (pinfunction "3_3") (pintype "passive"))
      (node (ref "U1") (pin "46") (pinfunction "PA13_46") (pintype "bidirectional"))
    )
    (net (code "68") (name "3.3V") (class "Default")
      (node (ref "C5") (pin "2") (pinfunction "2_2") (pintype "passive"))
      (node (ref "C6") (pin "2") (pinfunction "2_2") (pintype "passive"))
      (node (ref "C7") (pin "2") (pinfunction "2_2") (pintype "passive"))
      (node (ref "C8") (pin "2") (pinfunction "2_2") (pintype "passive"))
      (node (ref "C9") (pin "2") (pinfunction "2_2") (pintype "passive"))
      (node (ref "D1") (pin "2") (pinfunction "K_2") (pintype "passive"))
      (node (ref "D3") (pin "2") (pinfunction "K_2") (pintype "passive"))
      (node (ref "E2") (pin "1") (pinfunction "A_1") (pintype "passive"))
      (node (ref "IC1") (pin "1") (pinfunction "VDD33_1") (pintype "passive"))
      (node (ref "IC4") (pin "19") (pinfunction "STBY_19") (pintype "passive"))
      (node (ref "IC4") (pin "20") (pinfunction "VCC_20") (pintype "passive"))
      (node (ref "IC5") (pin "19") (pinfunction "STBY_19") (pintype "passive"))
      (node (ref "IC5") (pin "20") (pinfunction "VCC_20") (pintype "passive"))
      (node (ref "JP1") (pin "2") (pinfunction "VCC_2") (pintype "passive"))
      (node (ref "JP2") (pin "7") (pinfunction "7_7") (pintype "passive"))
      (node (ref "JP4") (pin "7") (pinfunction "7_7") (pintype "passive"))
      (node (ref "JP5") (pin "2") (pinfunction "2_2") (pintype "passive"))
      (node (ref "JP6") (pin "2") (pinfunction "2_2") (pintype "passive"))
      (node (ref "JP7") (pin "2") (pinfunction "2_2") (pintype "passive"))
      (node (ref "JP8") (pin "2") (pinfunction "2_2") (pintype "passive"))
      (node (ref "MX1") (pin "4") (pinfunction "4_4") (pintype "passive"))
      (node (ref "MX2") (pin "2") (pinfunction "2_2") (pintype "passive"))
      (node (ref "MX3") (pin "2") (pinfunction "2_2") (pintype "passive"))
      (node (ref "R1") (pin "2") (pinfunction "2_2") (pintype "passive"))
      (node (ref "R17") (pin "1") (pinfunction "1_1") (pintype "passive"))
      (node (ref "R2") (pin "2") (pinfunction "2_2") (pintype "passive"))
      (node (ref "R5") (pin "1") (pinfunction "1_1") (pintype "passive"))
      (node (ref "R6") (pin "2") (pinfunction "2_2") (pintype "passive"))
      (node (ref "R9") (pin "2") (pinfunction "2_2") (pintype "passive"))
      (node (ref "U1") (pin "1") (pinfunction "VBAT_1") (pintype "power_in"))
      (node (ref "U1") (pin "13") (pinfunction "VDDA_13") (pintype "power_in"))
      (node (ref "U1") (pin "19") (pinfunction "VDD_4_19") (pintype "power_in"))
      (node (ref "U1") (pin "32") (pinfunction "VDD_1_32") (pintype "power_in"))
      (node (ref "U1") (pin "48") (pinfunction "VDD_2_48") (pintype "power_in"))
      (node (ref "U1") (pin "64") (pinfunction "VDD_3_64") (pintype "power_in"))
      (node (ref "V1") (pin "2") (pinfunction "Vout_2") (pintype "passive"))
    )
    (net (code "69") (name "5V") (class "Default")
      (node (ref "E1") (pin "1") (pinfunction "A_1") (pintype "passive"))
      (node (ref "E3") (pin "1") (pinfunction "A_1") (pintype "passive"))
      (node (ref "IC2") (pin "4") (pinfunction "FB_4") (pintype "input"))
      (node (ref "JP2") (pin "8") (pinfunction "8_8") (pintype "passive"))
      (node (ref "JP4") (pin "8") (pinfunction "8_8") (pintype "passive"))
      (node (ref "L2") (pin "2") (pinfunction "2_2") (pintype "passive"))
      (node (ref "LS1") (pin "1") (pinfunction "1_1") (pintype "passive"))
      (node (ref "Moudle1") (pin "2") (pinfunction "VCC_2") (pintype "passive"))
      (node (ref "Moudle1") (pin "8") (pinfunction "VCC_8") (pintype "passive"))
      (node (ref "V1") (pin "3") (pinfunction "Vin_3") (pintype "passive"))
    )
    (net (code "70") (name "GND") (class "Default")
      (node (ref "C1") (pin "1") (pinfunction "1_1") (pintype "passive"))
      (node (ref "C10") (pin "1") (pinfunction "1_1") (pintype "passive"))
      (node (ref "C11") (pin "2") (pinfunction "2_2") (pintype "passive"))
      (node (ref "C12") (pin "2") (pinfunction "2_2") (pintype "passive"))
      (node (ref "C2") (pin "1") (pinfunction "1_1") (pintype "passive"))
      (node (ref "C3") (pin "1") (pinfunction "1_1") (pintype "passive"))
      (node (ref "C4") (pin "1") (pinfunction "1_1") (pintype "passive"))
      (node (ref "C5") (pin "1") (pinfunction "1_1") (pintype "passive"))
      (node (ref "C6") (pin "1") (pinfunction "1_1") (pintype "passive"))
      (node (ref "C7") (pin "1") (pinfunction "1_1") (pintype "passive"))
      (node (ref "C8") (pin "1") (pinfunction "1_1") (pintype "passive"))
      (node (ref "C9") (pin "1") (pinfunction "1_1") (pintype "passive"))
      (node (ref "D1") (pin "1") (pinfunction "A_1") (pintype "passive"))
      (node (ref "D3") (pin "1") (pinfunction "A_1") (pintype "passive"))
      (node (ref "D5") (pin "2") (pinfunction "K_2") (pintype "passive"))
      (node (ref "D7") (pin "1") (pinfunction "A_1") (pintype "passive"))
      (node (ref "E1") (pin "2") (pinfunction "K_2") (pintype "passive"))
      (node (ref "E2") (pin "2") (pinfunction "K_2") (pintype "passive"))
      (node (ref "E3") (pin "2") (pinfunction "K_2") (pintype "passive"))
      (node (ref "E4") (pin "2") (pinfunction "K_2") (pintype "passive"))
      (node (ref "E5") (pin "2") (pinfunction "K_2") (pintype "passive"))
      (node (ref "E6") (pin "2") (pinfunction "K_2") (pintype "passive"))
      (node (ref "IC1") (pin "10") (pinfunction "GPIO10_10") (pintype "passive"))
      (node (ref "IC1") (pin "9") (pinfunction "GND_9") (pintype "passive"))
      (node (ref "IC2") (pin "3") (pinfunction "GND_3") (pintype "power_in"))
      (node (ref "IC2") (pin "5") (pinfunction "~{ON}/OFF_5") (pintype "input"))
      (node (ref "IC3") (pin "2") (pinfunction "GND_2") (pintype "passive"))
      (node (ref "IC4") (pin "10") (pinfunction "PGND2_10") (pintype "passive"))
      (node (ref "IC4") (pin "18") (pinfunction "GND_18") (pintype "passive"))
      (node (ref "IC4") (pin "3") (pinfunction "PGND1_3") (pintype "passive"))
      (node (ref "IC4") (pin "4") (pinfunction "PGND1_4") (pintype "passive"))
      (node (ref "IC4") (pin "9") (pinfunction "PGND2_9") (pintype "passive"))
      (node (ref "IC5") (pin "10") (pinfunction "PGND2_10") (pintype "passive"))
      (node (ref "IC5") (pin "18") (pinfunction "GND_18") (pintype "passive"))
      (node (ref "IC5") (pin "3") (pinfunction "PGND1_3") (pintype "passive"))
      (node (ref "IC5") (pin "4") (pinfunction "PGND1_4") (pintype "passive"))
      (node (ref "IC5") (pin "9") (pinfunction "PGND2_9") (pintype "passive"))
      (node (ref "JP1") (pin "1") (pinfunction "GND_1") (pintype "passive"))
      (node (ref "JP2") (pin "6") (pinfunction "6_6") (pintype "passive"))
      (node (ref "JP3") (pin "1") (pinfunction "1_1") (pintype "passive"))
      (node (ref "JP4") (pin "5") (pinfunction "5_5") (pintype "passive"))
      (node (ref "JP4") (pin "6") (pinfunction "6_6") (pintype "passive"))
      (node (ref "JP5") (pin "5") (pinfunction "5_5") (pintype "passive"))
      (node (ref "JP6") (pin "5") (pinfunction "5_5") (pintype "passive"))
      (node (ref "JP7") (pin "5") (pinfunction "5_5") (pintype "passive"))
      (node (ref "JP8") (pin "5") (pinfunction "5_5") (pintype "passive"))
      (node (ref "MX1") (pin "2") (pinfunction "2_2") (pintype "passive"))
      (node (ref "MX2") (pin "1") (pinfunction "1_1") (pintype "passive"))
      (node (ref "MX3") (pin "1") (pinfunction "1_1") (pintype "passive"))
      (node (ref "Moudle1") (pin "11") (pinfunction "GND_11") (pintype "passive"))
      (node (ref "Moudle1") (pin "5") (pinfunction "GND_5") (pintype "passive"))
      (node (ref "Q1") (pin "3") (pinfunction "C_3") (pintype "passive"))
      (node (ref "R12") (pin "2") (pinfunction "2_2") (pintype "passive"))
      (node (ref "R13") (pin "2") (pinfunction "2_2") (pintype "passive"))
      (node (ref "R14") (pin "2") (pinfunction "2_2") (pintype "passive"))
      (node (ref "R15") (pin "2") (pinfunction "2_2") (pintype "passive"))
      (node (ref "R18") (pin "2") (pinfunction "2_2") (pintype "passive"))
      (node (ref "R19") (pin "1") (pinfunction "1_1") (pintype "passive"))
      (node (ref "R20") (pin "1") (pinfunction "1_1") (pintype "passive"))
      (node (ref "R21") (pin "2") (pinfunction "2_2") (pintype "passive"))
      (node (ref "R22") (pin "1") (pinfunction "1_1") (pintype "passive"))
      (node (ref "R4") (pin "1") (pinfunction "1_1") (pintype "passive"))
      (node (ref "R7") (pin "1") (pinfunction "1_1") (pintype "passive"))
      (node (ref "R8") (pin "1") (pinfunction "1_1") (pintype "passive"))
      (node (ref "ST-RST1") (pin "2") (pinfunction "2_2") (pintype "passive"))
      (node (ref "U1") (pin "12") (pinfunction "VSSA_12") (pintype "power_in"))
      (node (ref "U1") (pin "18") (pinfunction "VSS_4_18") (pintype "power_in"))
      (node (ref "U1") (pin "31") (pinfunction "VSS_1_31") (pintype "power_in"))
      (node (ref "U1") (pin "47") (pinfunction "VSS_2_47") (pintype "power_in"))
      (node (ref "U1") (pin "63") (pinfunction "VSS_3_63") (pintype "power_in"))
      (node (ref "USBC1") (pin "A1") (pinfunction "GND_A1") (pintype "passive"))
      (node (ref "USBC1") (pin "A12") (pinfunction "GND_A12") (pintype "passive"))
      (node (ref "USBC1") (pin "B1") (pinfunction "GND_B1") (pintype "passive"))
      (node (ref "USBC1") (pin "B12") (pinfunction "GND_B12") (pintype "passive"))
      (node (ref "USBC2") (pin "A1") (pinfunction "GND_A1") (pintype "passive"))
      (node (ref "USBC2") (pin "A12") (pinfunction "GND_A12") (pintype "passive"))
      (node (ref "USBC2") (pin "B1") (pinfunction "GND_B1") (pintype "passive"))
      (node (ref "USBC2") (pin "B12") (pinfunction "GND_B12") (pintype "passive"))
      (node (ref "V1") (pin "1") (pinfunction "GND_1") (pintype "passive"))
    )
    (net (code "71") (name "Net-(D2-A)") (class "Default")
      (node (ref "D2") (pin "1") (pinfunction "A_1") (pintype "passive"))
      (node (ref "R1") (pin "1") (pinfunction "1_1") (pintype "passive"))
    )
    (net (code "72") (name "Net-(D4-A)") (class "Default")
      (node (ref "D4") (pin "1") (pinfunction "A_1") (pintype "passive"))
      (node (ref "R6") (pin "1") (pinfunction "1_1") (pintype "passive"))
    )
    (net (code "73") (name "Net-(D5-A)") (class "Default")
      (node (ref "D5") (pin "1") (pinfunction "A_1") (pintype "passive"))
      (node (ref "R9") (pin "1") (pinfunction "1_1") (pintype "passive"))
    )
    (net (code "74") (name "Net-(D7-K)") (class "Default")
      (node (ref "D7") (pin "2") (pinfunction "K_2") (pintype "passive"))
      (node (ref "IC2") (pin "2") (pinfunction "OUT_2") (pintype "power_in"))
      (node (ref "L2") (pin "1") (pinfunction "1_1") (pintype "passive"))
    )
    (net (code "75") (name "Net-(D8-A)") (class "Default")
      (node (ref "D8") (pin "1") (pinfunction "A_1") (pintype "passive"))
      (node (ref "IC3") (pin "3") (pinfunction "LX_3") (pintype "passive"))
      (node (ref "L1") (pin "1") (pinfunction "1_1") (pintype "passive"))
    )
    (net (code "76") (name "Net-(D8-K)") (class "Default")
      (node (ref "C12") (pin "1") (pinfunction "1_1") (pintype "passive"))
      (node (ref "D8") (pin "2") (pinfunction "K_2") (pintype "passive"))
      (node (ref "IC3") (pin "4") (pinfunction "VBS_4") (pintype "passive"))
    )
    (net (code "77") (name "Net-(IC1-GPIO2)") (class "Default")
      (node (ref "IC1") (pin "16") (pinfunction "GPIO2_16") (pintype "passive"))
      (node (ref "R2") (pin "1") (pinfunction "1_1") (pintype "passive"))
    )
    (net (code "78") (name "Net-(IC3-ICHG)") (class "Default")
      (node (ref "IC3") (pin "6") (pinfunction "ICHG_6") (pintype "passive"))
      (node (ref "R20") (pin "2") (pinfunction "2_2") (pintype "passive"))
    )
    (net (code "79") (name "Net-(Q1-B)") (class "Default")
      (node (ref "Q1") (pin "1") (pinfunction "B_1") (pintype "passive"))
      (node (ref "R16") (pin "1") (pinfunction "1_1") (pintype "passive"))
    )
    (net (code "80") (name "Net-(Q1-E)") (class "Default")
      (node (ref "LS1") (pin "2") (pinfunction "2_2") (pintype "passive"))
      (node (ref "Q1") (pin "2") (pinfunction "E_2") (pintype "passive"))
    )
    (net (code "81") (name "Net-(R12-Pad1)") (class "Default")
      (node (ref "R12") (pin "1") (pinfunction "1_1") (pintype "passive"))
      (node (ref "S1") (pin "2") (pinfunction "2_2") (pintype "passive"))
    )
    (net (code "82") (name "Net-(R13-Pad1)") (class "Default")
      (node (ref "R13") (pin "1") (pinfunction "1_1") (pintype "passive"))
      (node (ref "S2") (pin "2") (pinfunction "2_2") (pintype "passive"))
    )
    (net (code "83") (name "Net-(R14-Pad1)") (class "Default")
      (node (ref "R14") (pin "1") (pinfunction "1_1") (pintype "passive"))
      (node (ref "S3") (pin "2") (pinfunction "2_2") (pintype "passive"))
    )
    (net (code "84") (name "Net-(R15-Pad1)") (class "Default")
      (node (ref "R15") (pin "1") (pinfunction "1_1") (pintype "passive"))
      (node (ref "S4") (pin "2") (pinfunction "2_2") (pintype "passive"))
    )
    (net (code "85") (name "Net-(USBC1-CC1)") (class "Default")
      (node (ref "R19") (pin "2") (pinfunction "2_2") (pintype "passive"))
      (node (ref "USBC1") (pin "A5") (pinfunction "CC1_A5") (pintype "passive"))
    )
    (net (code "86") (name "Net-(USBC1-CC2)") (class "Default")
      (node (ref "R18") (pin "1") (pinfunction "1_1") (pintype "passive"))
      (node (ref "USBC1") (pin "B5") (pinfunction "CC2_B5") (pintype "passive"))
    )
    (net (code "87") (name "Net-(USBC2-CC1)") (class "Default")
      (node (ref "R22") (pin "2") (pinfunction "2_2") (pintype "passive"))
      (node (ref "USBC2") (pin "A5") (pinfunction "CC1_A5") (pintype "passive"))
    )
    (net (code "88") (name "Net-(USBC2-CC2)") (class "Default")
      (node (ref "R21") (pin "1") (pinfunction "1_1") (pintype "passive"))
      (node (ref "USBC2") (pin "B5") (pinfunction "CC2_B5") (pintype "passive"))
    )
    (net (code "89") (name "V_BAT") (class "Default")
      (node (ref "C11") (pin "1") (pinfunction "1_1") (pintype "passive"))
      (node (ref "E4") (pin "1") (pinfunction "A_1") (pintype "passive"))
      (node (ref "E5") (pin "1") (pinfunction "A_1") (pintype "passive"))
      (node (ref "E6") (pin "1") (pinfunction "A_1") (pintype "passive"))
      (node (ref "IC2") (pin "1") (pinfunction "IN_1") (pintype "power_in"))
      (node (ref "IC3") (pin "5") (pinfunction "BAT_5") (pintype "passive"))
      (node (ref "IC4") (pin "13") (pinfunction "VM2_13") (pintype "passive"))
      (node (ref "IC4") (pin "14") (pinfunction "VM3_14") (pintype "passive"))
      (node (ref "IC4") (pin "24") (pinfunction "VM1_24") (pintype "passive"))
      (node (ref "IC5") (pin "13") (pinfunction "VM2_13") (pintype "passive"))
      (node (ref "IC5") (pin "14") (pinfunction "VM3_14") (pintype "passive"))
      (node (ref "IC5") (pin "24") (pinfunction "VM1_24") (pintype "passive"))
      (node (ref "JP3") (pin "2") (pinfunction "2_2") (pintype "passive"))
      (node (ref "R3") (pin "2") (pinfunction "2_2") (pintype "passive"))
    )
    (net (code "90") (name "V_USB") (class "Default")
      (node (ref "C10") (pin "2") (pinfunction "2_2") (pintype "passive"))
      (node (ref "IC3") (pin "1") (pinfunction "VIN_1") (pintype "passive"))
      (node (ref "IC3") (pin "7") (pinfunction "NTC_7") (pintype "passive"))
      (node (ref "L1") (pin "2") (pinfunction "2_2") (pintype "passive"))
      (node (ref "USBC1") (pin "A4") (pinfunction "VBUS_A4") (pintype "passive"))
      (node (ref "USBC1") (pin "A9") (pinfunction "VBUS_A9") (pintype "passive"))
      (node (ref "USBC1") (pin "B4") (pinfunction "VBUS_B4") (pintype "passive"))
      (node (ref "USBC1") (pin "B9") (pinfunction "VBUS_B9") (pintype "passive"))
      (node (ref "USBC2") (pin "A4") (pinfunction "VBUS_A4") (pintype "passive"))
      (node (ref "USBC2") (pin "A9") (pinfunction "VBUS_A9") (pintype "passive"))
      (node (ref "USBC2") (pin "B4") (pinfunction "VBUS_B4") (pintype "passive"))
      (node (ref "USBC2") (pin "B9") (pinfunction "VBUS_B9") (pintype "passive"))
    )
    (net (code "91") (name "unconnected-(IC1-GPIO0-Pad18)") (class "Default")
      (node (ref "IC1") (pin "18") (pinfunction "GPIO0_18") (pintype "passive+no_connect"))
    )
    (net (code "92") (name "unconnected-(IC1-GPIO3-Pad15)") (class "Default")
      (node (ref "IC1") (pin "15") (pinfunction "GPIO3_15") (pintype "passive+no_connect"))
    )
    (net (code "93") (name "unconnected-(JP2-Pad4)") (class "Default")
      (node (ref "JP2") (pin "4") (pinfunction "4_4") (pintype "passive"))
    )
    (net (code "94") (name "unconnected-(JP2-Pad5)") (class "Default")
      (node (ref "JP2") (pin "5") (pinfunction "5_5") (pintype "passive"))
    )
    (net (code "95") (name "unconnected-(Moudle1-D1-Pad6)") (class "Default")
      (node (ref "Moudle1") (pin "6") (pinfunction "D1_6") (pintype "passive+no_connect"))
    )
    (net (code "96") (name "unconnected-(Moudle1-D2-Pad7)") (class "Default")
      (node (ref "Moudle1") (pin "7") (pinfunction "D2_7") (pintype "passive+no_connect"))
    )
    (net (code "97") (name "unconnected-(Moudle1-D3-Pad12)") (class "Default")
      (node (ref "Moudle1") (pin "12") (pinfunction "D3_12") (pintype "passive+no_connect"))
    )
    (net (code "98") (name "unconnected-(Moudle1-DO-Pad1)") (class "Default")
      (node (ref "Moudle1") (pin "1") (pinfunction "DO_1") (pintype "passive+no_connect"))
    )
    (net (code "99") (name "unconnected-(Moudle1-SCL-Pad9)") (class "Default")
      (node (ref "Moudle1") (pin "9") (pinfunction "SCL_9") (pintype "passive+no_connect"))
    )
    (net (code "100") (name "unconnected-(Moudle1-SDA-Pad10)") (class "Default")
      (node (ref "Moudle1") (pin "10") (pinfunction "SDA_10") (pintype "passive+no_connect"))
    )
    (net (code "101") (name "unconnected-(U1A-PB1-Pad27)") (class "Default")
      (node (ref "U1") (pin "27") (pinfunction "PB1_27") (pintype "bidirectional"))
    )
    (net (code "102") (name "unconnected-(U1A-PB10-Pad29)") (class "Default")
      (node (ref "U1") (pin "29") (pinfunction "PB10_29") (pintype "bidirectional"))
    )
    (net (code "103") (name "unconnected-(U1A-PB11-Pad30)") (class "Default")
      (node (ref "U1") (pin "30") (pinfunction "PB11_30") (pintype "bidirectional"))
    )
    (net (code "104") (name "unconnected-(U1A-PC13-TAMPER-RTC-Pad2)") (class "Default")
      (node (ref "U1") (pin "2") (pinfunction "PC13-TAMPER-RTC_2") (pintype "bidirectional"))
    )
    (net (code "105") (name "unconnected-(USBC1-Pad0)") (class "Default")
      (node (ref "USBC1") (pin "0") (pinfunction "0_0") (pintype "passive+no_connect"))
    )
    (net (code "106") (name "unconnected-(USBC1-Pad0)_1") (class "Default")
      (node (ref "USBC1") (pin "0") (pinfunction "0_0") (pintype "passive+no_connect"))
    )
    (net (code "107") (name "unconnected-(USBC1-Pad0)_2") (class "Default")
      (node (ref "USBC1") (pin "0") (pinfunction "0_0") (pintype "passive+no_connect"))
    )
    (net (code "108") (name "unconnected-(USBC1-Pad0)_3") (class "Default")
      (node (ref "USBC1") (pin "0") (pinfunction "0_0") (pintype "passive+no_connect"))
    )
    (net (code "109") (name "unconnected-(USBC1-SBU1-PadA8)") (class "Default")
      (node (ref "USBC1") (pin "A8") (pinfunction "SBU1_A8") (pintype "passive+no_connect"))
    )
    (net (code "110") (name "unconnected-(USBC1-SBU2-PadB8)") (class "Default")
      (node (ref "USBC1") (pin "B8") (pinfunction "SBU2_B8") (pintype "passive+no_connect"))
    )
    (net (code "111") (name "unconnected-(USBC2-Pad0)") (class "Default")
      (node (ref "USBC2") (pin "0") (pinfunction "0_0") (pintype "passive+no_connect"))
    )
    (net (code "112") (name "unconnected-(USBC2-Pad0)_1") (class "Default")
      (node (ref "USBC2") (pin "0") (pinfunction "0_0") (pintype "passive+no_connect"))
    )
    (net (code "113") (name "unconnected-(USBC2-Pad0)_2") (class "Default")
      (node (ref "USBC2") (pin "0") (pinfunction "0_0") (pintype "passive+no_connect"))
    )
    (net (code "114") (name "unconnected-(USBC2-Pad0)_3") (class "Default")
      (node (ref "USBC2") (pin "0") (pinfunction "0_0") (pintype "passive+no_connect"))
    )
    (net (code "115") (name "unconnected-(USBC2-SBU1-PadA8)") (class "Default")
      (node (ref "USBC2") (pin "A8") (pinfunction "SBU1_A8") (pintype "passive+no_connect"))
    )
    (net (code "116") (name "unconnected-(USBC2-SBU2-PadB8)") (class "Default")
      (node (ref "USBC2") (pin "B8") (pinfunction "SBU2_B8") (pintype "passive+no_connect"))
    )
  )
)
